# main.net
KiCad netlist of a schematic drawn in Altium Designer
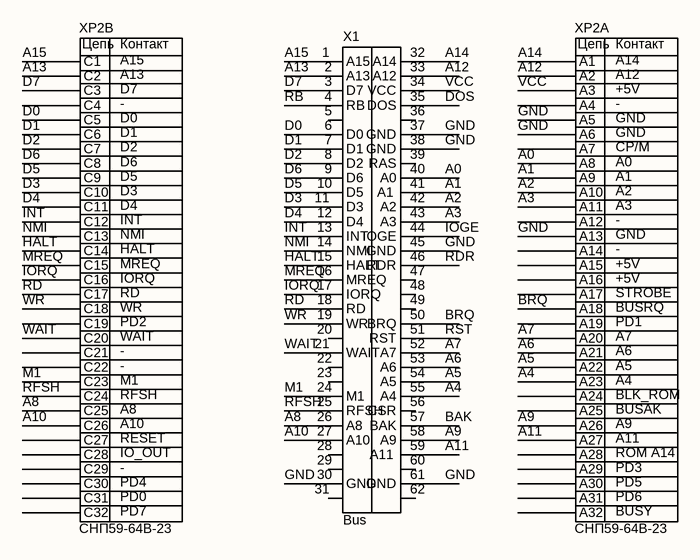
[diagram p0: main.SchDoc]

(export (version "E")
  (design (tool "Eeschema 10.0.6"))
  (components
    (comp (ref "X1") (value "Bus") (footprint "BUS") (libsource (lib "Connectors") (part "Bus")))
    (comp (ref "XP2")
      (value "СНП59-64В-23")
      (footprint "delta-host")
      (libsource (lib "Connectors") (part "СНП59-64В-23"))
    )
  )
  (nets
    (net (code "1") (name "/A0") (class "Default")
      (node (ref "X1") (pin "40") (pinfunction "A0_40") (pintype "passive"))
      (node (ref "XP2") (pin "A8") (pinfunction "A8_A8") (pintype "passive"))
    )
    (net (code "2") (name "/A1") (class "Default")
      (node (ref "X1") (pin "41") (pinfunction "A1_41") (pintype "passive"))
      (node (ref "XP2") (pin "A9") (pinfunction "A9_A9") (pintype "passive"))
    )
    (net (code "3") (name "/A2") (class "Default")
      (node (ref "X1") (pin "42") (pinfunction "A2_42") (pintype "passive"))
      (node (ref "XP2") (pin "A10") (pinfunction "A10_A10") (pintype "passive"))
    )
    (net (code "4") (name "/A3") (class "Default")
      (node (ref "X1") (pin "43") (pinfunction "A3_43") (pintype "passive"))
      (node (ref "XP2") (pin "A11") (pinfunction "A11_A11") (pintype "passive"))
    )
    (net (code "5") (name "/A4") (class "Default")
      (node (ref "X1") (pin "55") (pinfunction "A4_55") (pintype "passive"))
      (node (ref "XP2") (pin "A23") (pinfunction "A23_A23") (pintype "passive"))
    )
    (net (code "6") (name "/A5") (class "Default")
      (node (ref "X1") (pin "54") (pinfunction "A5_54") (pintype "passive"))
      (node (ref "XP2") (pin "A22") (pinfunction "A22_A22") (pintype "passive"))
    )
    (net (code "7") (name "/A6") (class "Default")
      (node (ref "X1") (pin "53") (pinfunction "A6_53") (pintype "passive"))
      (node (ref "XP2") (pin "A21") (pinfunction "A21_A21") (pintype "passive"))
    )
    (net (code "8") (name "/A7") (class "Default")
      (node (ref "X1") (pin "52") (pinfunction "A7_52") (pintype "passive"))
      (node (ref "XP2") (pin "A20") (pinfunction "A20_A20") (pintype "passive"))
    )
    (net (code "9") (name "/A8") (class "Default")
      (node (ref "X1") (pin "26") (pinfunction "A8_26") (pintype "passive"))
      (node (ref "XP2") (pin "C25") (pinfunction "C25_C25") (pintype "passive"))
    )
    (net (code "10") (name "/A9") (class "Default")
      (node (ref "X1") (pin "58") (pinfunction "A9_58") (pintype "passive"))
      (node (ref "XP2") (pin "A26") (pinfunction "A26_A26") (pintype "passive"))
    )
    (net (code "11") (name "/A10") (class "Default")
      (node (ref "X1") (pin "27") (pinfunction "A10_27") (pintype "passive"))
      (node (ref "XP2") (pin "C26") (pinfunction "C26_C26") (pintype "passive"))
    )
    (net (code "12") (name "/A11") (class "Default")
      (node (ref "X1") (pin "59") (pinfunction "A11_59") (pintype "passive"))
      (node (ref "XP2") (pin "A27") (pinfunction "A27_A27") (pintype "passive"))
    )
    (net (code "13") (name "/A12") (class "Default")
      (node (ref "X1") (pin "33") (pinfunction "A12_33") (pintype "passive"))
      (node (ref "XP2") (pin "A2") (pinfunction "A2_A2") (pintype "passive"))
    )
    (net (code "14") (name "/A13") (class "Default")
      (node (ref "X1") (pin "2") (pinfunction "A13_2") (pintype "passive"))
      (node (ref "XP2") (pin "C2") (pinfunction "C2_C2") (pintype "passive"))
    )
    (net (code "15") (name "/A14") (class "Default")
      (node (ref "X1") (pin "32") (pinfunction "A14_32") (pintype "passive"))
      (node (ref "XP2") (pin "A1") (pinfunction "A1_A1") (pintype "passive"))
    )
    (net (code "16") (name "/A15") (class "Default")
      (node (ref "X1") (pin "1") (pinfunction "A15_1") (pintype "passive"))
      (node (ref "XP2") (pin "C1") (pinfunction "C1_C1") (pintype "passive"))
    )
    (net (code "17") (name "/BAK") (class "Default")
      (node (ref "X1") (pin "57") (pinfunction "BAK_57") (pintype "passive"))
    )
    (net (code "18") (name "/BRQ") (class "Default")
      (node (ref "X1") (pin "50") (pinfunction "BRQ_50") (pintype "passive"))
      (node (ref "XP2") (pin "A18") (pinfunction "A18_A18") (pintype "passive"))
    )
    (net (code "19") (name "/D0") (class "Default")
      (node (ref "X1") (pin "6") (pinfunction "D0_6") (pintype "passive"))
      (node (ref "XP2") (pin "C5") (pinfunction "C5_C5") (pintype "passive"))
    )
    (net (code "20") (name "/D1") (class "Default")
      (node (ref "X1") (pin "7") (pinfunction "D1_7") (pintype "passive"))
      (node (ref "XP2") (pin "C6") (pinfunction "C6_C6") (pintype "passive"))
    )
    (net (code "21") (name "/D2") (class "Default")
      (node (ref "X1") (pin "8") (pinfunction "D2_8") (pintype "passive"))
      (node (ref "XP2") (pin "C7") (pinfunction "C7_C7") (pintype "passive"))
    )
    (net (code "22") (name "/D3") (class "Default")
      (node (ref "X1") (pin "11") (pinfunction "D3_11") (pintype "passive"))
      (node (ref "XP2") (pin "C10") (pinfunction "C10_C10") (pintype "passive"))
    )
    (net (code "23") (name "/D4") (class "Default")
      (node (ref "X1") (pin "12") (pinfunction "D4_12") (pintype "passive"))
      (node (ref "XP2") (pin "C11") (pinfunction "C11_C11") (pintype "passive"))
    )
    (net (code "24") (name "/D5") (class "Default")
      (node (ref "X1") (pin "10") (pinfunction "D5_10") (pintype "passive"))
      (node (ref "XP2") (pin "C9") (pinfunction "C9_C9") (pintype "passive"))
    )
    (net (code "25") (name "/D6") (class "Default")
      (node (ref "X1") (pin "9") (pinfunction "D6_9") (pintype "passive"))
      (node (ref "XP2") (pin "C8") (pinfunction "C8_C8") (pintype "passive"))
    )
    (net (code "26") (name "/D7") (class "Default")
      (node (ref "X1") (pin "3") (pinfunction "D7_3") (pintype "passive"))
      (node (ref "XP2") (pin "C3") (pinfunction "C3_C3") (pintype "passive"))
    )
    (net (code "27") (name "/DOS") (class "Default")
      (node (ref "X1") (pin "35") (pinfunction "DOS_35") (pintype "passive"))
    )
    (net (code "28") (name "/GND") (class "Default")
      (node (ref "X1") (pin "30") (pinfunction "GND_30") (pintype "passive"))
      (node (ref "X1") (pin "37") (pinfunction "GND_37") (pintype "passive"))
      (node (ref "X1") (pin "38") (pinfunction "GND_38") (pintype "passive"))
      (node (ref "X1") (pin "45") (pinfunction "GND_45") (pintype "passive"))
      (node (ref "X1") (pin "61") (pinfunction "GND_61") (pintype "passive"))
      (node (ref "XP2") (pin "A13") (pinfunction "A13_A13") (pintype "passive"))
      (node (ref "XP2") (pin "A5") (pinfunction "A5_A5") (pintype "passive"))
      (node (ref "XP2") (pin "A6") (pinfunction "A6_A6") (pintype "passive"))
    )
    (net (code "29") (name "/HALT") (class "Default")
      (node (ref "X1") (pin "15") (pinfunction "HALT_15") (pintype "passive"))
      (node (ref "XP2") (pin "C14") (pinfunction "C14_C14") (pintype "passive"))
    )
    (net (code "30") (name "/INT") (class "Default")
      (node (ref "X1") (pin "13") (pinfunction "INT_13") (pintype "passive"))
      (node (ref "XP2") (pin "C12") (pinfunction "C12_C12") (pintype "passive"))
    )
    (net (code "31") (name "/IOGE") (class "Default")
      (node (ref "X1") (pin "44") (pinfunction "IOGE_44") (pintype "passive"))
    )
    (net (code "32") (name "/IORQ") (class "Default")
      (node (ref "X1") (pin "17") (pinfunction "IORQ_17") (pintype "passive"))
      (node (ref "XP2") (pin "C16") (pinfunction "C16_C16") (pintype "passive"))
    )
    (net (code "33") (name "/M1") (class "Default")
      (node (ref "X1") (pin "24") (pinfunction "M1_24") (pintype "passive"))
      (node (ref "XP2") (pin "C23") (pinfunction "C23_C23") (pintype "passive"))
    )
    (net (code "34") (name "/MREQ") (class "Default")
      (node (ref "X1") (pin "16") (pinfunction "MREQ_16") (pintype "passive"))
      (node (ref "XP2") (pin "C15") (pinfunction "C15_C15") (pintype "passive"))
    )
    (net (code "35") (name "/NMI") (class "Default")
      (node (ref "X1") (pin "14") (pinfunction "NMI_14") (pintype "passive"))
      (node (ref "XP2") (pin "C13") (pinfunction "C13_C13") (pintype "passive"))
    )
    (net (code "36") (name "/RB") (class "Default")
      (node (ref "X1") (pin "4") (pinfunction "RB_4") (pintype "passive"))
    )
    (net (code "37") (name "/RD") (class "Default")
      (node (ref "X1") (pin "18") (pinfunction "RD_18") (pintype "passive"))
      (node (ref "XP2") (pin "C17") (pinfunction "C17_C17") (pintype "passive"))
    )
    (net (code "38") (name "/RDR") (class "Default")
      (node (ref "X1") (pin "46") (pinfunction "RDR_46") (pintype "passive"))
    )
    (net (code "39") (name "/RFSH") (class "Default")
      (node (ref "X1") (pin "25") (pinfunction "RFSH_25") (pintype "passive"))
      (node (ref "XP2") (pin "C24") (pinfunction "C24_C24") (pintype "passive"))
    )
    (net (code "40") (name "/RST") (class "Default")
      (node (ref "X1") (pin "51") (pinfunction "RST_51") (pintype "passive"))
    )
    (net (code "41") (name "/VCC") (class "Default")
      (node (ref "X1") (pin "34") (pinfunction "VCC_34") (pintype "passive"))
      (node (ref "XP2") (pin "A3") (pinfunction "A3_A3") (pintype "passive"))
    )
    (net (code "42") (name "/WAIT") (class "Default")
      (node (ref "X1") (pin "21") (pinfunction "WAIT_21") (pintype "passive"))
      (node (ref "XP2") (pin "C20") (pinfunction "C20_C20") (pintype "passive"))
    )
    (net (code "43") (name "/WR") (class "Default")
      (node (ref "X1") (pin "19") (pinfunction "WR_19") (pintype "passive"))
      (node (ref "XP2") (pin "C18") (pinfunction "C18_C18") (pintype "passive"))
    )
    (net (code "44") (name "unconnected-(X1-CSR-Pad56)") (class "Default")
      (node (ref "X1") (pin "56") (pinfunction "CSR_56") (pintype "passive"))
    )
    (net (code "45") (name "unconnected-(X1-Pad5)") (class "Default")
      (node (ref "X1") (pin "5") (pintype "passive"))
    )
    (net (code "46") (name "unconnected-(X1-Pad20)") (class "Default")
      (node (ref "X1") (pin "20") (pintype "passive"))
    )
    (net (code "47") (name "unconnected-(X1-Pad22)") (class "Default")
      (node (ref "X1") (pin "22") (pintype "passive"))
    )
    (net (code "48") (name "unconnected-(X1-Pad23)") (class "Default")
      (node (ref "X1") (pin "23") (pintype "passive"))
    )
    (net (code "49") (name "unconnected-(X1-Pad28)") (class "Default")
      (node (ref "X1") (pin "28") (pintype "passive"))
    )
    (net (code "50") (name "unconnected-(X1-Pad29)") (class "Default")
      (node (ref "X1") (pin "29") (pintype "passive"))
    )
    (net (code "51") (name "unconnected-(X1-Pad31)") (class "Default")
      (node (ref "X1") (pin "31") (pintype "passive"))
    )
    (net (code "52") (name "unconnected-(X1-Pad36)") (class "Default")
      (node (ref "X1") (pin "36") (pintype "passive"))
    )
    (net (code "53") (name "unconnected-(X1-Pad47)") (class "Default")
      (node (ref "X1") (pin "47") (pintype "passive"))
    )
    (net (code "54") (name "unconnected-(X1-Pad48)") (class "Default")
      (node (ref "X1") (pin "48") (pintype "passive"))
    )
    (net (code "55") (name "unconnected-(X1-Pad49)") (class "Default")
      (node (ref "X1") (pin "49") (pintype "passive"))
    )
    (net (code "56") (name "unconnected-(X1-Pad60)") (class "Default")
      (node (ref "X1") (pin "60") (pintype "passive"))
    )
    (net (code "57") (name "unconnected-(X1-Pad62)") (class "Default")
      (node (ref "X1") (pin "62") (pintype "passive"))
    )
    (net (code "58") (name "unconnected-(X1-RAS-Pad39)") (class "Default")
      (node (ref "X1") (pin "39") (pinfunction "RAS_39") (pintype "passive"))
    )
    (net (code "59") (name "unconnected-(XP2-PadA4)") (class "Default")
      (node (ref "XP2") (pin "A4") (pinfunction "A4_A4") (pintype "passive"))
    )
    (net (code "60") (name "unconnected-(XP2-PadA7)") (class "Default")
      (node (ref "XP2") (pin "A7") (pinfunction "A7_A7") (pintype "passive"))
    )
    (net (code "61") (name "unconnected-(XP2-PadA12)") (class "Default")
      (node (ref "XP2") (pin "A12") (pinfunction "A12_A12") (pintype "passive"))
    )
    (net (code "62") (name "unconnected-(XP2-PadA14)") (class "Default")
      (node (ref "XP2") (pin "A14") (pinfunction "A14_A14") (pintype "passive"))
    )
    (net (code "63") (name "unconnected-(XP2-PadA15)") (class "Default")
      (node (ref "XP2") (pin "A15") (pinfunction "A15_A15") (pintype "passive"))
    )
    (net (code "64") (name "unconnected-(XP2-PadA16)") (class "Default")
      (node (ref "XP2") (pin "A16") (pinfunction "A16_A16") (pintype "passive"))
    )
    (net (code "65") (name "unconnected-(XP2-PadA17)") (class "Default")
      (node (ref "XP2") (pin "A17") (pinfunction "A17_A17") (pintype "passive"))
    )
    (net (code "66") (name "unconnected-(XP2-PadA19)") (class "Default")
      (node (ref "XP2") (pin "A19") (pinfunction "A19_A19") (pintype "passive"))
    )
    (net (code "67") (name "unconnected-(XP2-PadA24)") (class "Default")
      (node (ref "XP2") (pin "A24") (pinfunction "A24_A24") (pintype "passive"))
    )
    (net (code "68") (name "unconnected-(XP2-PadA25)") (class "Default")
      (node (ref "XP2") (pin "A25") (pinfunction "A25_A25") (pintype "passive"))
    )
    (net (code "69") (name "unconnected-(XP2-PadA28)") (class "Default")
      (node (ref "XP2") (pin "A28") (pinfunction "A28_A28") (pintype "passive"))
    )
    (net (code "70") (name "unconnected-(XP2-PadA29)") (class "Default")
      (node (ref "XP2") (pin "A29") (pinfunction "A29_A29") (pintype "passive"))
    )
    (net (code "71") (name "unconnected-(XP2-PadA30)") (class "Default")
      (node (ref "XP2") (pin "A30") (pinfunction "A30_A30") (pintype "passive"))
    )
    (net (code "72") (name "unconnected-(XP2-PadA31)") (class "Default")
      (node (ref "XP2") (pin "A31") (pinfunction "A31_A31") (pintype "passive"))
    )
    (net (code "73") (name "unconnected-(XP2-PadA32)") (class "Default")
      (node (ref "XP2") (pin "A32") (pinfunction "A32_A32") (pintype "passive"))
    )
    (net (code "74") (name "unconnected-(XP2-PadC4)") (class "Default")
      (node (ref "XP2") (pin "C4") (pinfunction "C4_C4") (pintype "passive"))
    )
    (net (code "75") (name "unconnected-(XP2-PadC19)") (class "Default")
      (node (ref "XP2") (pin "C19") (pinfunction "C19_C19") (pintype "passive"))
    )
    (net (code "76") (name "unconnected-(XP2-PadC21)") (class "Default")
      (node (ref "XP2") (pin "C21") (pinfunction "C21_C21") (pintype "passive"))
    )
    (net (code "77") (name "unconnected-(XP2-PadC22)") (class "Default")
      (node (ref "XP2") (pin "C22") (pinfunction "C22_C22") (pintype "passive"))
    )
    (net (code "78") (name "unconnected-(XP2-PadC27)") (class "Default")
      (node (ref "XP2") (pin "C27") (pinfunction "C27_C27") (pintype "passive"))
    )
    (net (code "79") (name "unconnected-(XP2-PadC28)") (class "Default")
      (node (ref "XP2") (pin "C28") (pinfunction "C28_C28") (pintype "passive"))
    )
    (net (code "80") (name "unconnected-(XP2-PadC29)") (class "Default")
      (node (ref "XP2") (pin "C29") (pinfunction "C29_C29") (pintype "passive"))
    )
    (net (code "81") (name "unconnected-(XP2-PadC30)") (class "Default")
      (node (ref "XP2") (pin "C30") (pinfunction "C30_C30") (pintype "passive"))
    )
    (net (code "82") (name "unconnected-(XP2-PadC31)") (class "Default")
      (node (ref "XP2") (pin "C31") (pinfunction "C31_C31") (pintype "passive"))
    )
    (net (code "83") (name "unconnected-(XP2-PadC32)") (class "Default")
      (node (ref "XP2") (pin "C32") (pinfunction "C32_C32") (pintype "passive"))
    )
  )
)
